# 2Leonardo_PCB.net
KiCad netlist of a schematic drawn in Altium Designer
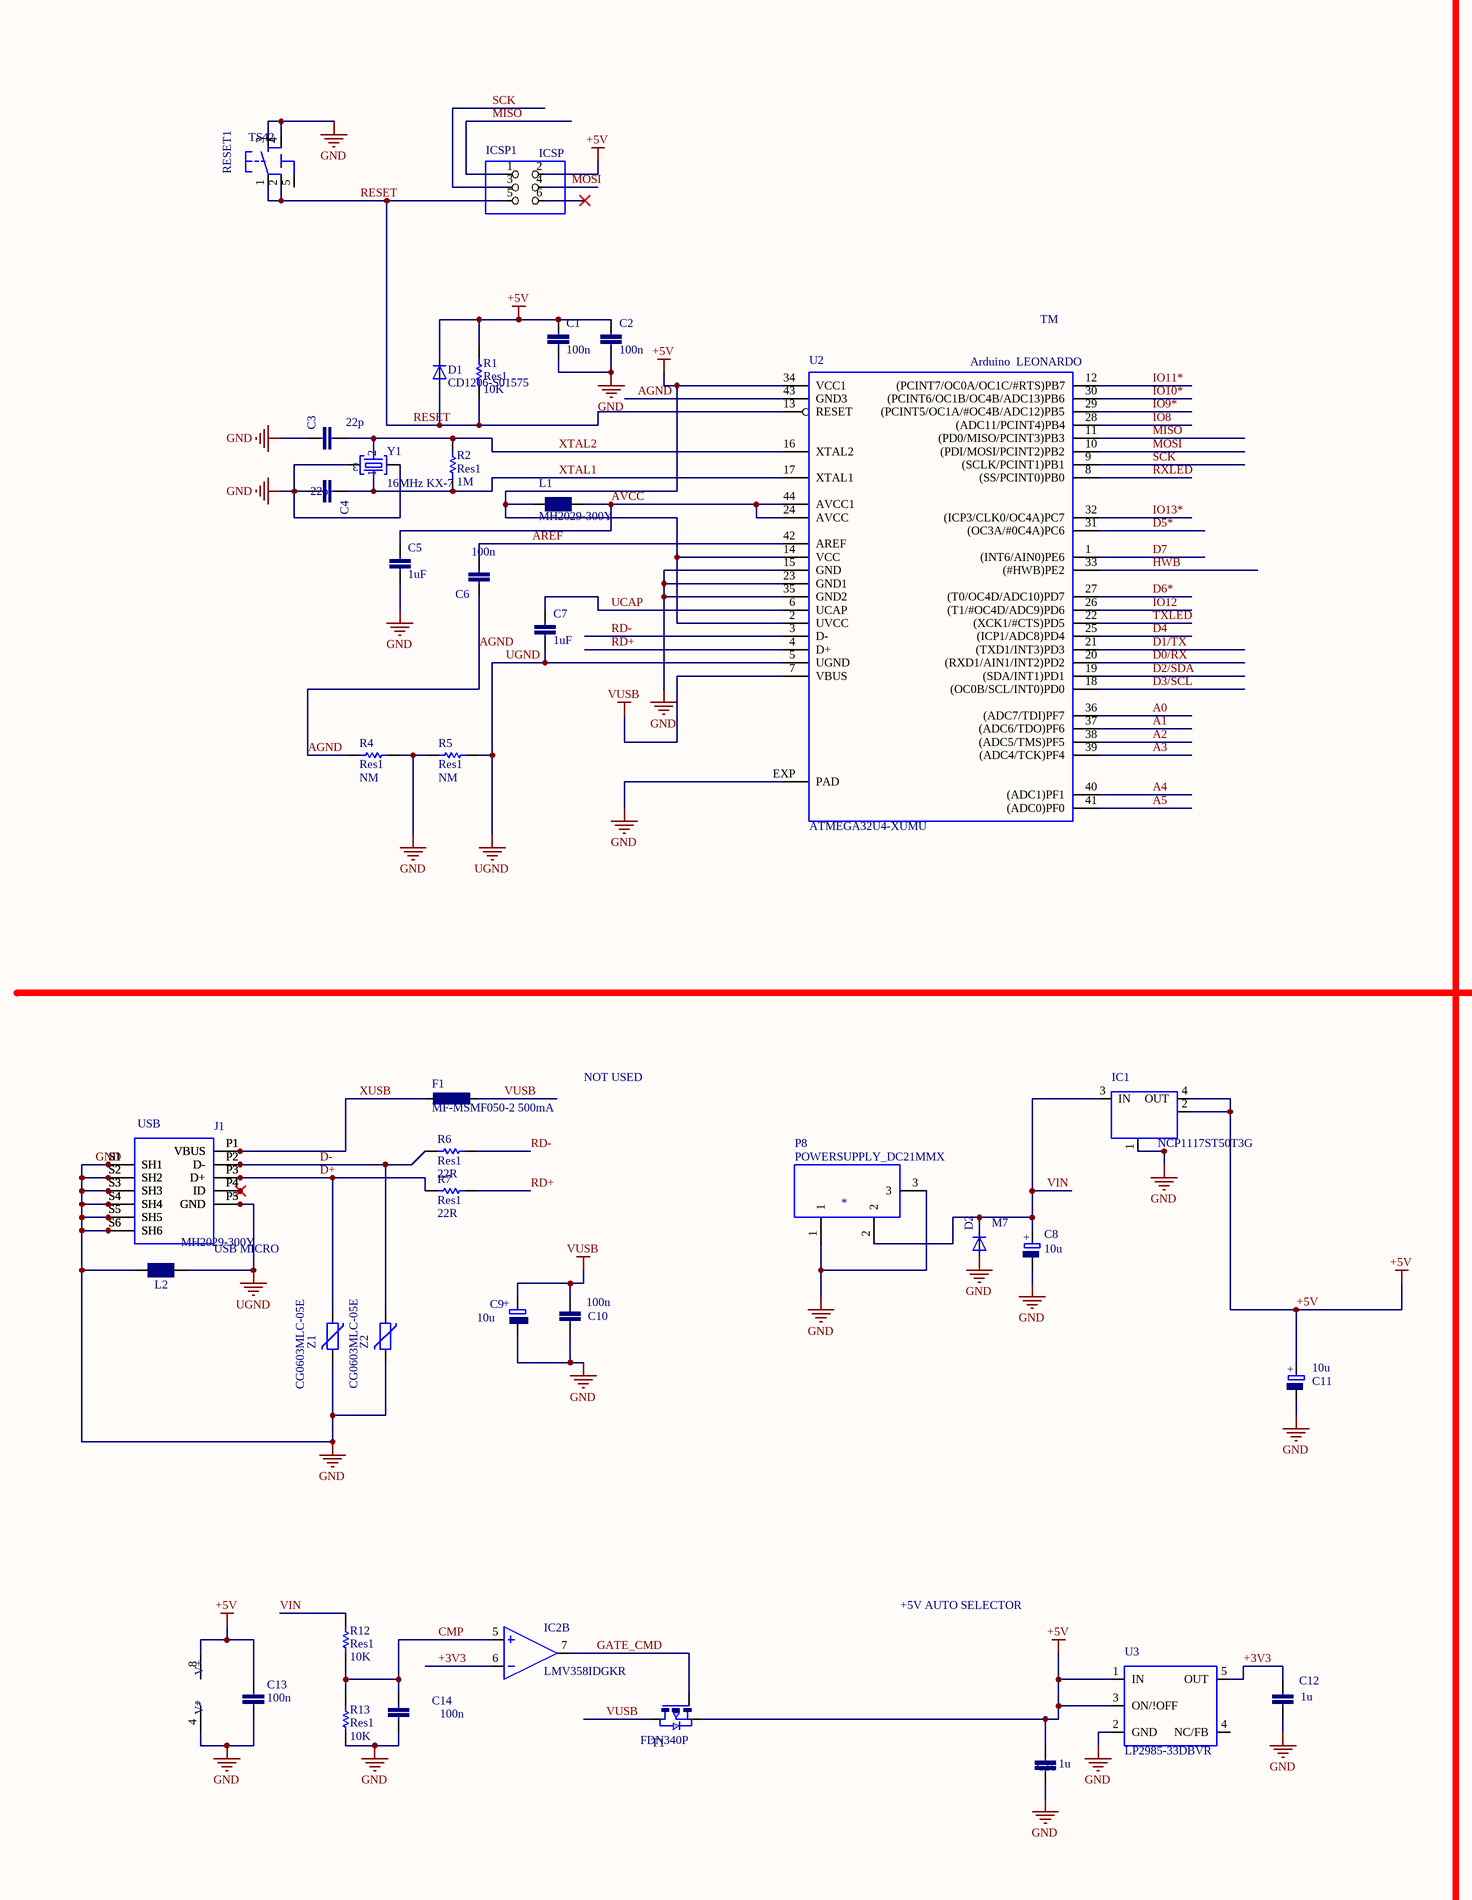
[diagram p0: 2Leonardo_PCB.SchDoc, left]
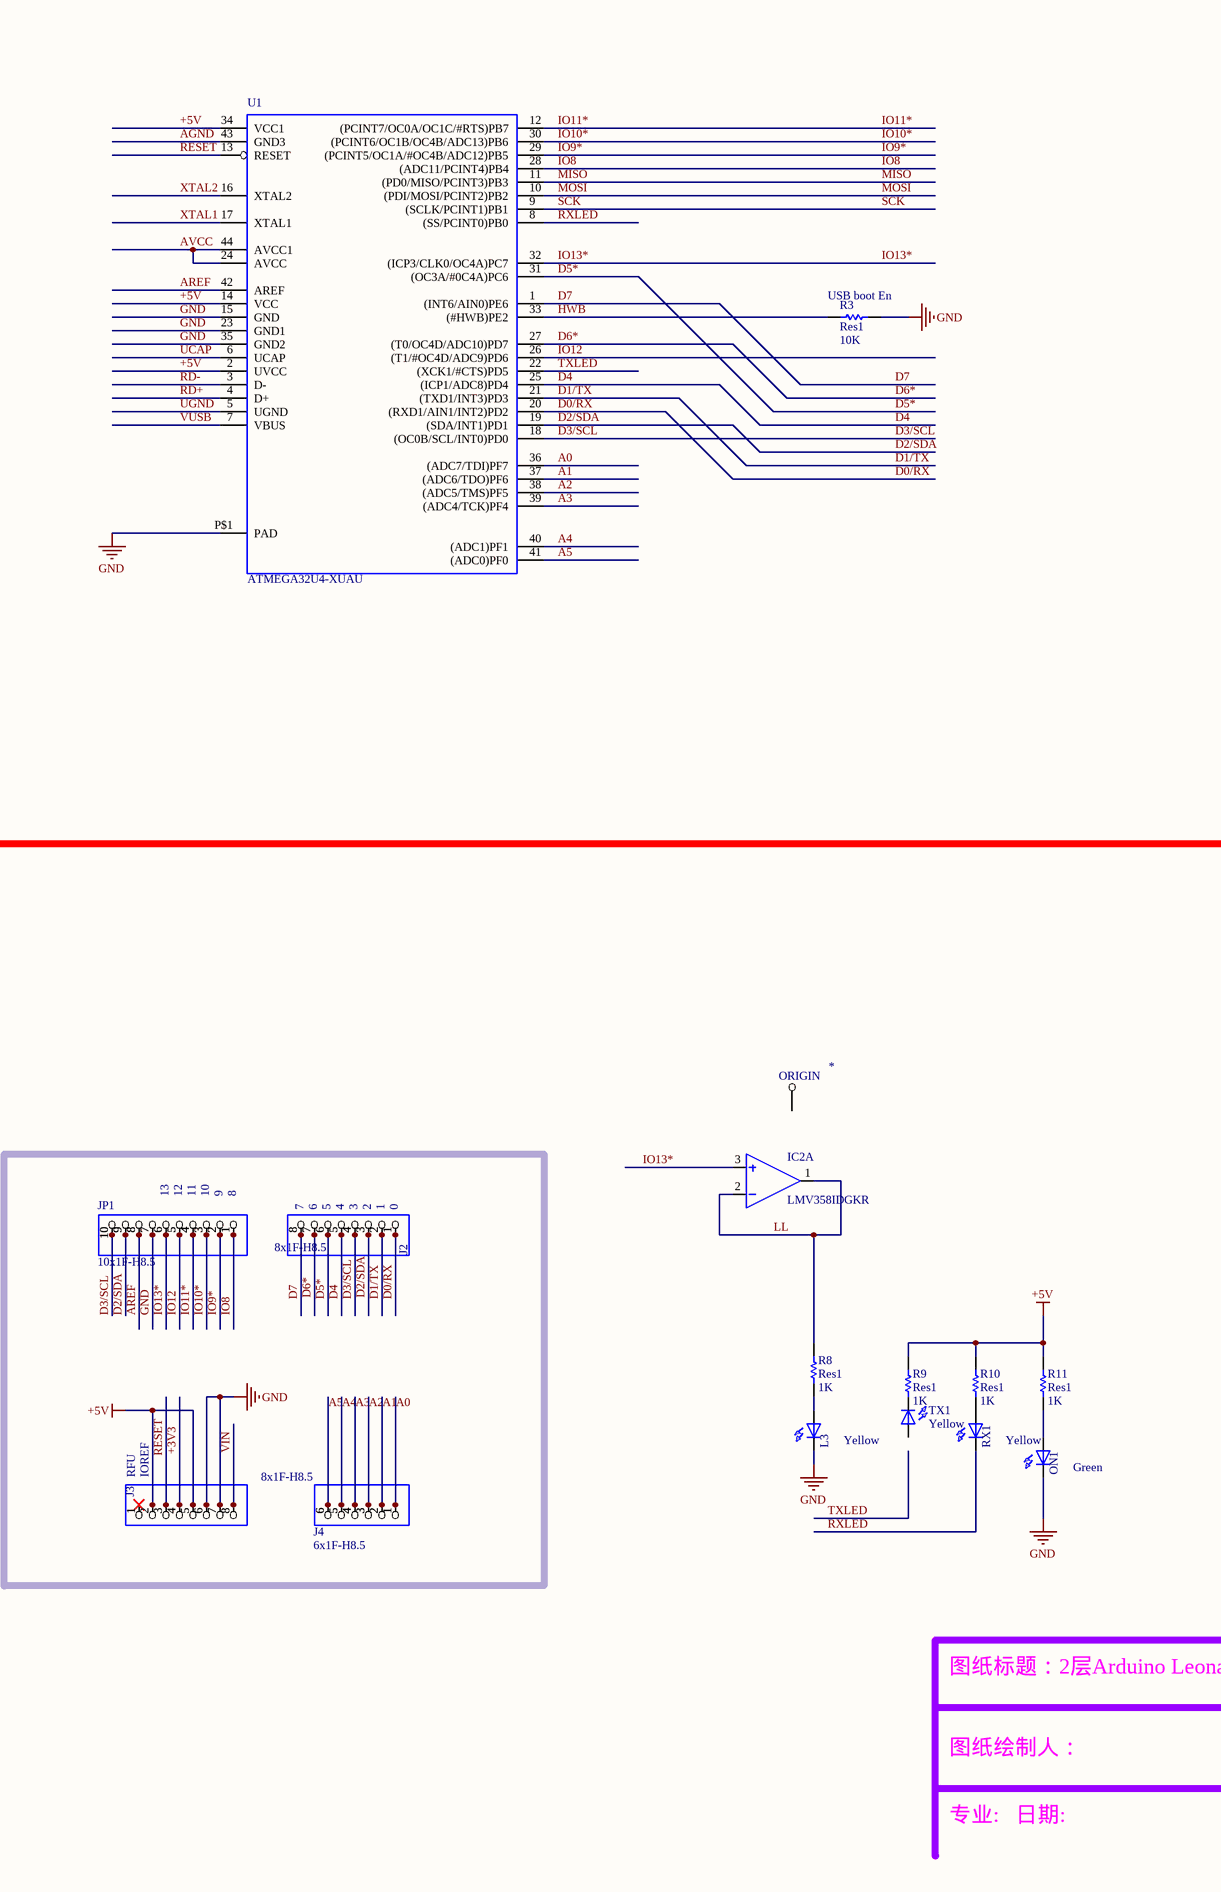
[diagram p1: 2Leonardo_PCB.SchDoc, right]

(export (version "E")
  (design (tool "Eeschema 10.0.6"))
  (components
    (comp (ref "C1") (value "100n") (footprint "C0603-ROUND") (libsource (lib "SmartPrj") (part "C-EUC0603")))
    (comp (ref "C2") (value "100n") (footprint "C0603-ROUND") (libsource (lib "SmartPrj") (part "C-EUC0603")))
    (comp (ref "C3") (value "22p") (footprint "C0603-ROUND") (libsource (lib "") (part "C-EUC0603_1")))
    (comp (ref "C4") (value "22p") (footprint "C0603-ROUND") (libsource (lib "") (part "C-EUC0603_3")))
    (comp (ref "C5") (value "1uF") (footprint "C0603-ROUND") (libsource (lib "SmartPrj") (part "C-EUC0603")))
    (comp (ref "C6") (value "100n") (footprint "C0603-ROUND") (libsource (lib "") (part "C-EUC0603_2")))
    (comp (ref "C7") (value "1uF") (footprint "C0603-ROUND") (libsource (lib "SmartPrj") (part "C-EUC0603")))
    (comp (ref "C8") (value "10u") (footprint "SMC_B") (libsource (lib "") (part "CPOL-EUSMCB_1")))
    (comp (ref "C9") (value "10u") (footprint "SMC_B") (libsource (lib "rcl") (part "CPOL-EUSMCB")))
    (comp (ref "C10") (value "100n") (footprint "C0603-ROUND") (libsource (lib "") (part "C-EUC0603_1")))
    (comp (ref "C11") (value "10u") (footprint "SMC_B") (libsource (lib "") (part "CPOL-EUSMCB_1")))
    (comp (ref "C12") (value "1u") (footprint "C0603-ROUND") (libsource (lib "") (part "C-EUC0603_2")))
    (comp (ref "C13")
      (value "100n")
      (footprint "C0603-ROUND")
      (libsource (lib "SmartPrj") (part "C-EUC0603"))
    )
    (comp (ref "C14") (value "100n") (footprint "C0603-ROUND") (libsource (lib "") (part "C-EUC0603_1")))
    (comp (ref "C15") (value "1u") (footprint "C0603-ROUND") (libsource (lib "") (part "C-EUC0603_1")))
    (comp (ref "D1")
      (value "CD1206-S01575")
      (footprint "MINIMELF")
      (libsource (lib "Leonardo") (part "DIODE-MINIMELF"))
    )
    (comp (ref "D2") (value "M7") (footprint "SMB") (libsource (lib "diode") (part "DIODE-SMB")))
    (comp (ref "F1")
      (value "MF-MSMF050-2 500mA")
      (footprint "L1812")
      (libsource (lib "rcl") (part "L-EUL1812"))
    )
    (comp (ref "IC1")
      (value "NCP1117ST50T3G")
      (footprint "SOT223")
      (libsource (lib "linear") (part "MC33269ST-3.3T3"))
    )
    (comp (ref "IC2")
      (value "LMV358IDGKR")
      (footprint "MSOP08")
      (libsource (lib "linear") (part "LMV358MMX"))
    )
    (comp (ref "ICSP1") (value "ICSP") (footprint "2X03") (libsource (lib "SmartPrj") (part "PINHD-2X3")))
    (comp (ref "J1")
      (value "USB MICRO")
      (footprint "CON2_USB_MICRO_B_AT")
      (libsource (lib "SmartPrj") (part "MYCON2_USB-MINI-B"))
    )
    (comp (ref "J2") (value "8x1F-H8.5") (footprint "1X08") (libsource (lib "SmartPrj") (part "PINHD-1X8")))
    (comp (ref "J3") (value "8x1F-H8.5") (footprint "1X08") (libsource (lib "SmartPrj") (part "PINHD-1X8")))
    (comp (ref "J4") (value "6x1F-H8.5") (footprint "1X06") (libsource (lib "Leonardo") (part "PINHD-1X6")))
    (comp (ref "JP1")
      (value "10x1F-H8.5")
      (footprint "1X10")
      (libsource (lib "Leonardo") (part "PINHD-1X10"))
    )
    (comp (ref "L1") (value "MH2029-300Y") (footprint "0805") (libsource (lib "") (part "WE-CBF_0805_1")))
    (comp (ref "L2")
      (value "MH2029-300Y")
      (footprint "0805")
      (libsource (lib "wuerth-elektronik") (part "WE-CBF_0805"))
    )
    (comp (ref "L3")
      (value "Yellow")
      (footprint "CHIPLED_0805")
      (libsource (lib "led") (part "LEDCHIPLED_0805"))
    )
    (comp (ref "ON1")
      (value "Green")
      (footprint "CHIPLED_0805")
      (libsource (lib "led") (part "LEDCHIPLED_0805"))
    )
    (comp (ref "ORIGIN1") (value "*") (footprint "FIDUCIA-MOUNT") (libsource (lib "SmartPrj") (part "TP_SP")))
    (comp (ref "P1")
      (value "*")
      (footprint "POWERSUPPLY_DC-21MM")
      (libsource (lib "SmartPrj") (part "POWERSUPPLY_DC21MMX"))
    )
    (comp (ref "R1")
      (value "Res1")
      (footprint "R0603-ROUND")
      (description "Resistor")
      (fields (field (name "ALTIUM_VALUE") "10K") (field (name "PUBLISHER") "Altium Limited"))
      (libsource (lib "Miscellaneous Devices") (part "Res1"))
    )
    (comp (ref "R2")
      (value "Res1")
      (footprint "R0603-ROUND")
      (description "Resistor")
      (fields (field (name "ALTIUM_VALUE") "1M") (field (name "PUBLISHER") "Altium Limited"))
      (libsource (lib "Miscellaneous Devices") (part "Res1"))
    )
    (comp (ref "R3")
      (value "Res1")
      (footprint "R0603-ROUND")
      (description "Resistor")
      (fields (field (name "ALTIUM_VALUE") "10K") (field (name "PUBLISHER") "Altium Limited"))
      (libsource (lib "Miscellaneous Devices") (part "Res1"))
    )
    (comp (ref "R4")
      (value "Res1")
      (footprint "R0603-ROUND")
      (description "Resistor")
      (fields (field (name "ALTIUM_VALUE") "NM") (field (name "PUBLISHER") "Altium Limited"))
      (libsource (lib "Miscellaneous Devices") (part "Res1"))
    )
    (comp (ref "R5")
      (value "Res1")
      (footprint "R0603-ROUND")
      (description "Resistor")
      (fields (field (name "ALTIUM_VALUE") "NM") (field (name "PUBLISHER") "Altium Limited"))
      (libsource (lib "Miscellaneous Devices") (part "Res1"))
    )
    (comp (ref "R6")
      (value "Res1")
      (footprint "R0603-ROUND")
      (description "Resistor")
      (fields (field (name "ALTIUM_VALUE") "22R") (field (name "PUBLISHER") "Altium Limited"))
      (libsource (lib "Miscellaneous Devices") (part "Res1"))
    )
    (comp (ref "R7")
      (value "Res1")
      (footprint "R0603-ROUND")
      (description "Resistor")
      (fields (field (name "ALTIUM_VALUE") "22R") (field (name "PUBLISHER") "Altium Limited"))
      (libsource (lib "Miscellaneous Devices") (part "Res1"))
    )
    (comp (ref "R8")
      (value "Res1")
      (footprint "R0603-ROUND")
      (description "Resistor")
      (fields (field (name "ALTIUM_VALUE") "1K") (field (name "PUBLISHER") "Altium Limited"))
      (libsource (lib "Miscellaneous Devices") (part "Res1"))
    )
    (comp (ref "R9")
      (value "Res1")
      (footprint "R0603-ROUND")
      (description "Resistor")
      (fields (field (name "ALTIUM_VALUE") "1K") (field (name "PUBLISHER") "Altium Limited"))
      (libsource (lib "Miscellaneous Devices") (part "Res1"))
    )
    (comp (ref "R10")
      (value "Res1")
      (footprint "R0603-ROUND")
      (description "Resistor")
      (fields (field (name "ALTIUM_VALUE") "1K") (field (name "PUBLISHER") "Altium Limited"))
      (libsource (lib "Miscellaneous Devices") (part "Res1"))
    )
    (comp (ref "R11")
      (value "Res1")
      (footprint "R0603-ROUND")
      (description "Resistor")
      (fields (field (name "ALTIUM_VALUE") "1K") (field (name "PUBLISHER") "Altium Limited"))
      (libsource (lib "Miscellaneous Devices") (part "Res1"))
    )
    (comp (ref "R12")
      (value "Res1")
      (footprint "R0603-ROUND")
      (description "Resistor")
      (fields (field (name "ALTIUM_VALUE") "10K") (field (name "PUBLISHER") "Altium Limited"))
      (libsource (lib "Miscellaneous Devices") (part "Res1"))
    )
    (comp (ref "R13")
      (value "Res1")
      (footprint "R0603-ROUND")
      (description "Resistor")
      (fields (field (name "ALTIUM_VALUE") "10K") (field (name "PUBLISHER") "Altium Limited"))
      (libsource (lib "Miscellaneous Devices") (part "Res1"))
    )
    (comp (ref "RESET1") (value "TS42") (footprint "TS42") (libsource (lib "SmartPrj") (part "TS42")))
    (comp (ref "RX1")
      (value "Yellow")
      (footprint "CHIPLED_0805")
      (libsource (lib "led") (part "LEDCHIPLED_0805"))
    )
    (comp (ref "T1") (value "FDN340P") (footprint "SOT-23") (libsource (lib "zetex") (part "PMOSSOT23")))
    (comp (ref "TX1")
      (value "Yellow")
      (footprint "CHIPLED_0805")
      (libsource (lib "led") (part "LEDCHIPLED_0805"))
    )
    (comp (ref "U1")
      (value "ATMEGA32U4-XUAU")
      (footprint "TQFP44-PAD")
      (libsource (lib "SmartPrj") (part "ATMEGA32U4-XUAU"))
    )
    (comp (ref "U2")
      (value "ATMEGA32U4-XUMU")
      (footprint "QFN44ML7X7")
      (libsource (lib "SmartPrj") (part "ATMEGA32U4-XUMU"))
    )
    (comp (ref "U3")
      (value "LP2985-33DBVR")
      (footprint "SOT23-DBV")
      (libsource (lib "SmartPrj") (part "LP2985-XXDBVR33"))
    )
    (comp (ref "Y1")
      (value "16MHz KX-7")
      (footprint "CRYSTAL-3.2-2.5")
      (libsource (lib "SmartPrj") (part "CRYSTAL-3.2-2.5"))
    )
    (comp (ref "Z1")
      (value "CG0603MLC-05E")
      (footprint "CT/CN0603")
      (libsource (lib "varistor") (part "VARISTORCN0603"))
    )
    (comp (ref "Z2")
      (value "CG0603MLC-05E")
      (footprint "CT/CN0603")
      (libsource (lib "varistor") (part "VARISTORCN0603"))
    )
  )
  (nets
    (net (code "1") (name "+5V") (class "Default")
      (node (ref "C1") (pin "1") (pinfunction "1_1") (pintype "passive"))
      (node (ref "C11") (pin "+") (pinfunction "+_+") (pintype "passive"))
      (node (ref "C13") (pin "1") (pinfunction "1_1") (pintype "passive"))
      (node (ref "C15") (pin "2") (pinfunction "2_2") (pintype "passive"))
      (node (ref "C2") (pin "1") (pinfunction "1_1") (pintype "passive"))
      (node (ref "D1") (pin "C") (pinfunction "C_C") (pintype "passive"))
      (node (ref "IC1") (pin "2") (pinfunction "OUT@1_2") (pintype "passive"))
      (node (ref "IC1") (pin "4") (pinfunction "OUT_4") (pintype "passive"))
      (node (ref "IC2") (pin "8") (pinfunction "V+_8") (pintype "passive"))
      (node (ref "ICSP1") (pin "2") (pinfunction "2_2") (pintype "passive"))
      (node (ref "J3") (pin "2") (pinfunction "2_2") (pintype "passive"))
      (node (ref "J3") (pin "5") (pinfunction "5_5") (pintype "passive"))
      (node (ref "L1") (pin "1") (pinfunction "1_1") (pintype "passive"))
      (node (ref "R1") (pin "2") (pinfunction "2_2") (pintype "passive"))
      (node (ref "R10") (pin "2") (pinfunction "2_2") (pintype "passive"))
      (node (ref "R11") (pin "2") (pinfunction "2_2") (pintype "passive"))
      (node (ref "R9") (pin "2") (pinfunction "2_2") (pintype "passive"))
      (node (ref "T1") (pin "2") (pinfunction "S_2") (pintype "passive"))
      (node (ref "U1") (pin "14") (pinfunction "VCC_14") (pintype "passive"))
      (node (ref "U1") (pin "2") (pinfunction "UVCC_2") (pintype "passive"))
      (node (ref "U1") (pin "34") (pinfunction "VCC1_34") (pintype "passive"))
      (node (ref "U2") (pin "14") (pinfunction "VCC_14") (pintype "passive"))
      (node (ref "U2") (pin "2") (pinfunction "UVCC_2") (pintype "passive"))
      (node (ref "U2") (pin "34") (pinfunction "VCC1_34") (pintype "passive"))
      (node (ref "U3") (pin "1") (pinfunction "IN_1") (pintype "passive"))
      (node (ref "U3") (pin "3") (pinfunction "ON/!OFF_3") (pintype "passive"))
    )
    (net (code "2") (name "/+3V3") (class "Default")
      (node (ref "C12") (pin "2") (pinfunction "2_2") (pintype "passive"))
      (node (ref "IC2") (pin "6") (pinfunction "-IN_6") (pintype "passive"))
      (node (ref "J3") (pin "4") (pinfunction "4_4") (pintype "passive"))
      (node (ref "U3") (pin "5") (pinfunction "OUT_5") (pintype "passive"))
    )
    (net (code "3") (name "/A0") (class "Default")
      (node (ref "J4") (pin "1") (pinfunction "1_1") (pintype "passive"))
      (node (ref "U1") (pin "36") (pinfunction "(ADC7/TDI)PF7_36") (pintype "passive"))
      (node (ref "U2") (pin "36") (pinfunction "(ADC7/TDI)PF7_36") (pintype "passive"))
    )
    (net (code "4") (name "/A1") (class "Default")
      (node (ref "J4") (pin "2") (pinfunction "2_2") (pintype "passive"))
      (node (ref "U1") (pin "37") (pinfunction "(ADC6/TDO)PF6_37") (pintype "passive"))
      (node (ref "U2") (pin "37") (pinfunction "(ADC6/TDO)PF6_37") (pintype "passive"))
    )
    (net (code "5") (name "/A2") (class "Default")
      (node (ref "J4") (pin "3") (pinfunction "3_3") (pintype "passive"))
      (node (ref "U1") (pin "38") (pinfunction "(ADC5/TMS)PF5_38") (pintype "passive"))
      (node (ref "U2") (pin "38") (pinfunction "(ADC5/TMS)PF5_38") (pintype "passive"))
    )
    (net (code "6") (name "/A3") (class "Default")
      (node (ref "J4") (pin "4") (pinfunction "4_4") (pintype "passive"))
      (node (ref "U1") (pin "39") (pinfunction "(ADC4/TCK)PF4_39") (pintype "passive"))
      (node (ref "U2") (pin "39") (pinfunction "(ADC4/TCK)PF4_39") (pintype "passive"))
    )
    (net (code "7") (name "/A4") (class "Default")
      (node (ref "J4") (pin "5") (pinfunction "5_5") (pintype "passive"))
      (node (ref "U1") (pin "40") (pinfunction "(ADC1)PF1_40") (pintype "passive"))
      (node (ref "U2") (pin "40") (pinfunction "(ADC1)PF1_40") (pintype "passive"))
    )
    (net (code "8") (name "/A5") (class "Default")
      (node (ref "J4") (pin "6") (pinfunction "6_6") (pintype "passive"))
      (node (ref "U1") (pin "41") (pinfunction "(ADC0)PF0_41") (pintype "passive"))
      (node (ref "U2") (pin "41") (pinfunction "(ADC0)PF0_41") (pintype "passive"))
    )
    (net (code "9") (name "/AGND") (class "Default")
      (node (ref "C6") (pin "1") (pinfunction "1_1") (pintype "passive"))
      (node (ref "R4") (pin "1") (pinfunction "1_1") (pintype "passive"))
      (node (ref "U1") (pin "43") (pinfunction "GND3_43") (pintype "passive"))
      (node (ref "U2") (pin "43") (pinfunction "GND3_43") (pintype "passive"))
    )
    (net (code "10") (name "/AREF") (class "Default")
      (node (ref "C6") (pin "2") (pinfunction "2_2") (pintype "passive"))
      (node (ref "JP1") (pin "8") (pinfunction "8_8") (pintype "passive"))
      (node (ref "U1") (pin "42") (pinfunction "AREF_42") (pintype "passive"))
      (node (ref "U2") (pin "42") (pinfunction "AREF_42") (pintype "passive"))
    )
    (net (code "11") (name "/AVCC") (class "Default")
      (node (ref "C5") (pin "1") (pinfunction "1_1") (pintype "passive"))
      (node (ref "L1") (pin "2") (pinfunction "2_2") (pintype "passive"))
      (node (ref "U1") (pin "24") (pinfunction "AVCC_24") (pintype "passive"))
      (node (ref "U1") (pin "44") (pinfunction "AVCC1_44") (pintype "passive"))
      (node (ref "U2") (pin "24") (pinfunction "AVCC_24") (pintype "passive"))
      (node (ref "U2") (pin "44") (pinfunction "AVCC1_44") (pintype "passive"))
    )
    (net (code "12") (name "/CMP") (class "Default")
      (node (ref "C14") (pin "2") (pinfunction "2_2") (pintype "passive"))
      (node (ref "IC2") (pin "5") (pinfunction "+IN_5") (pintype "passive"))
      (node (ref "R12") (pin "1") (pinfunction "1_1") (pintype "passive"))
      (node (ref "R13") (pin "2") (pinfunction "2_2") (pintype "passive"))
    )
    (net (code "13") (name "/D+") (class "Default")
      (node (ref "J1") (pin "P3") (pinfunction "D+_P3") (pintype "passive"))
      (node (ref "R7") (pin "1") (pinfunction "1_1") (pintype "passive"))
      (node (ref "Z1") (pin "1") (pinfunction "1_1") (pintype "passive"))
    )
    (net (code "14") (name "/D-") (class "Default")
      (node (ref "J1") (pin "P2") (pinfunction "D-_P2") (pintype "passive"))
      (node (ref "R6") (pin "1") (pinfunction "1_1") (pintype "passive"))
      (node (ref "Z2") (pin "1") (pinfunction "1_1") (pintype "passive"))
    )
    (net (code "15") (name "/D0{slash}RX") (class "Default")
      (node (ref "J2") (pin "1") (pinfunction "1_1") (pintype "passive"))
      (node (ref "U1") (pin "20") (pinfunction "(RXD1/AIN1/INT2)PD2_20") (pintype "passive"))
      (node (ref "U2") (pin "20") (pinfunction "(RXD1/AIN1/INT2)PD2_20") (pintype "passive"))
    )
    (net (code "16") (name "/D1{slash}TX") (class "Default")
      (node (ref "J2") (pin "2") (pinfunction "2_2") (pintype "passive"))
      (node (ref "U1") (pin "21") (pinfunction "(TXD1/INT3)PD3_21") (pintype "passive"))
      (node (ref "U2") (pin "21") (pinfunction "(TXD1/INT3)PD3_21") (pintype "passive"))
    )
    (net (code "17") (name "/D2{slash}SDA") (class "Default")
      (node (ref "J2") (pin "3") (pinfunction "3_3") (pintype "passive"))
      (node (ref "JP1") (pin "9") (pinfunction "9_9") (pintype "passive"))
      (node (ref "U1") (pin "19") (pinfunction "(SDA/INT1)PD1_19") (pintype "passive"))
      (node (ref "U2") (pin "19") (pinfunction "(SDA/INT1)PD1_19") (pintype "passive"))
    )
    (net (code "18") (name "/D3{slash}SCL") (class "Default")
      (node (ref "J2") (pin "4") (pinfunction "4_4") (pintype "passive"))
      (node (ref "JP1") (pin "10") (pinfunction "10_10") (pintype "passive"))
      (node (ref "U1") (pin "18") (pinfunction "(OC0B/SCL/INT0)PD0_18") (pintype "passive"))
      (node (ref "U2") (pin "18") (pinfunction "(OC0B/SCL/INT0)PD0_18") (pintype "passive"))
    )
    (net (code "19") (name "/D4") (class "Default")
      (node (ref "J2") (pin "5") (pinfunction "5_5") (pintype "passive"))
      (node (ref "U1") (pin "25") (pinfunction "(ICP1/ADC8)PD4_25") (pintype "passive"))
      (node (ref "U2") (pin "25") (pinfunction "(ICP1/ADC8)PD4_25") (pintype "passive"))
    )
    (net (code "20") (name "/D5*") (class "Default")
      (node (ref "J2") (pin "6") (pinfunction "6_6") (pintype "passive"))
      (node (ref "U1") (pin "31") (pinfunction "(OC3A/#0C4A)PC6_31") (pintype "passive"))
      (node (ref "U2") (pin "31") (pinfunction "(OC3A/#0C4A)PC6_31") (pintype "passive"))
    )
    (net (code "21") (name "/D6*") (class "Default")
      (node (ref "J2") (pin "7") (pinfunction "7_7") (pintype "passive"))
      (node (ref "U1") (pin "27") (pinfunction "(T0/OC4D/ADC10)PD7_27") (pintype "passive"))
      (node (ref "U2") (pin "27") (pinfunction "(T0/OC4D/ADC10)PD7_27") (pintype "passive"))
    )
    (net (code "22") (name "/D7") (class "Default")
      (node (ref "J2") (pin "8") (pinfunction "8_8") (pintype "passive"))
      (node (ref "U1") (pin "1") (pinfunction "(INT6/AIN0)PE6_1") (pintype "passive"))
      (node (ref "U2") (pin "1") (pinfunction "(INT6/AIN0)PE6_1") (pintype "passive"))
    )
    (net (code "23") (name "/GATE_CMD") (class "Default")
      (node (ref "IC2") (pin "7") (pinfunction "OUT_7") (pintype "passive"))
      (node (ref "T1") (pin "3") (pinfunction "G_3") (pintype "passive"))
    )
    (net (code "24") (name "/HWB") (class "Default")
      (node (ref "R3") (pin "2") (pinfunction "2_2") (pintype "passive"))
      (node (ref "U1") (pin "33") (pinfunction "(#HWB)PE2_33") (pintype "passive"))
      (node (ref "U2") (pin "33") (pinfunction "(#HWB)PE2_33") (pintype "passive"))
    )
    (net (code "25") (name "/IO8") (class "Default")
      (node (ref "JP1") (pin "1") (pinfunction "1_1") (pintype "passive"))
      (node (ref "U1") (pin "28") (pinfunction "(ADC11/PCINT4)PB4_28") (pintype "passive"))
      (node (ref "U2") (pin "28") (pinfunction "(ADC11/PCINT4)PB4_28") (pintype "passive"))
    )
    (net (code "26") (name "/IO9*") (class "Default")
      (node (ref "JP1") (pin "2") (pinfunction "2_2") (pintype "passive"))
      (node (ref "U1") (pin "29") (pinfunction "(PCINT5/OC1A/#OC4B/ADC12)PB5_29") (pintype "passive"))
      (node (ref "U2") (pin "29") (pinfunction "(PCINT5/OC1A/#OC4B/ADC12)PB5_29") (pintype "passive"))
    )
    (net (code "27") (name "/IO10*") (class "Default")
      (node (ref "JP1") (pin "3") (pinfunction "3_3") (pintype "passive"))
      (node (ref "U1") (pin "30") (pinfunction "(PCINT6/OC1B/OC4B/ADC13)PB6_30") (pintype "passive"))
      (node (ref "U2") (pin "30") (pinfunction "(PCINT6/OC1B/OC4B/ADC13)PB6_30") (pintype "passive"))
    )
    (net (code "28") (name "/IO11*") (class "Default")
      (node (ref "JP1") (pin "4") (pinfunction "4_4") (pintype "passive"))
      (node (ref "U1") (pin "12") (pinfunction "(PCINT7/OC0A/OC1C/#RTS)PB7_12") (pintype "passive"))
      (node (ref "U2") (pin "12") (pinfunction "(PCINT7/OC0A/OC1C/#RTS)PB7_12") (pintype "passive"))
    )
    (net (code "29") (name "/IO12") (class "Default")
      (node (ref "JP1") (pin "5") (pinfunction "5_5") (pintype "passive"))
      (node (ref "U1") (pin "26") (pinfunction "(T1/#OC4D/ADC9)PD6_26") (pintype "passive"))
      (node (ref "U2") (pin "26") (pinfunction "(T1/#OC4D/ADC9)PD6_26") (pintype "passive"))
    )
    (net (code "30") (name "/IO13*") (class "Default")
      (node (ref "IC2") (pin "3") (pinfunction "+IN_3") (pintype "passive"))
      (node (ref "JP1") (pin "6") (pinfunction "6_6") (pintype "passive"))
      (node (ref "U1") (pin "32") (pinfunction "(ICP3/CLK0/OC4A)PC7_32") (pintype "passive"))
      (node (ref "U2") (pin "32") (pinfunction "(ICP3/CLK0/OC4A)PC7_32") (pintype "passive"))
    )
    (net (code "31") (name "/LL") (class "Default")
      (node (ref "IC2") (pin "1") (pinfunction "OUT_1") (pintype "passive"))
      (node (ref "IC2") (pin "2") (pinfunction "-IN_2") (pintype "passive"))
      (node (ref "R8") (pin "2") (pinfunction "2_2") (pintype "passive"))
    )
    (net (code "32") (name "/MISO") (class "Default")
      (node (ref "ICSP1") (pin "1") (pinfunction "1_1") (pintype "passive"))
      (node (ref "U1") (pin "11") (pinfunction "(PD0/MISO/PCINT3)PB3_11") (pintype "passive"))
      (node (ref "U2") (pin "11") (pinfunction "(PD0/MISO/PCINT3)PB3_11") (pintype "passive"))
    )
    (net (code "33") (name "/MOSI") (class "Default")
      (node (ref "ICSP1") (pin "4") (pinfunction "4_4") (pintype "passive"))
      (node (ref "U1") (pin "10") (pinfunction "(PDI/MOSI/PCINT2)PB2_10") (pintype "passive"))
      (node (ref "U2") (pin "10") (pinfunction "(PDI/MOSI/PCINT2)PB2_10") (pintype "passive"))
    )
    (net (code "34") (name "/RD+") (class "Default")
      (node (ref "R7") (pin "2") (pinfunction "2_2") (pintype "passive"))
      (node (ref "U1") (pin "4") (pinfunction "D+_4") (pintype "passive"))
      (node (ref "U2") (pin "4") (pinfunction "D+_4") (pintype "passive"))
    )
    (net (code "35") (name "/RD-") (class "Default")
      (node (ref "R6") (pin "2") (pinfunction "2_2") (pintype "passive"))
      (node (ref "U1") (pin "3") (pinfunction "D-_3") (pintype "passive"))
      (node (ref "U2") (pin "3") (pinfunction "D-_3") (pintype "passive"))
    )
    (net (code "36") (name "/RESET") (class "Default")
      (node (ref "D1") (pin "A") (pinfunction "A_A") (pintype "passive"))
      (node (ref "ICSP1") (pin "5") (pinfunction "5_5") (pintype "passive"))
      (node (ref "J3") (pin "3") (pinfunction "3_3") (pintype "passive"))
      (node (ref "R1") (pin "1") (pinfunction "1_1") (pintype "passive"))
      (node (ref "RESET1") (pin "1") (pinfunction "1_1") (pintype "passive"))
      (node (ref "RESET1") (pin "2") (pinfunction "2_2") (pintype "passive"))
      (node (ref "U1") (pin "13") (pinfunction "RESET_13") (pintype "passive"))
      (node (ref "U2") (pin "13") (pinfunction "RESET_13") (pintype "passive"))
    )
    (net (code "37") (name "/RXLED") (class "Default")
      (node (ref "RX1") (pin "C") (pinfunction "C_C") (pintype "passive"))
      (node (ref "U1") (pin "8") (pinfunction "(SS/PCINT0)PB0_8") (pintype "passive"))
      (node (ref "U2") (pin "8") (pinfunction "(SS/PCINT0)PB0_8") (pintype "passive"))
    )
    (net (code "38") (name "/SCK") (class "Default")
      (node (ref "ICSP1") (pin "3") (pinfunction "3_3") (pintype "passive"))
      (node (ref "U1") (pin "9") (pinfunction "(SCLK/PCINT1)PB1_9") (pintype "passive"))
      (node (ref "U2") (pin "9") (pinfunction "(SCLK/PCINT1)PB1_9") (pintype "passive"))
    )
    (net (code "39") (name "/TXLED") (class "Default")
      (node (ref "U1") (pin "22") (pinfunction "(XCK1/#CTS)PD5_22") (pintype "passive"))
      (node (ref "U2") (pin "22") (pinfunction "(XCK1/#CTS)PD5_22") (pintype "passive"))
    )
    (net (code "40") (name "/UCAP") (class "Default")
      (node (ref "C7") (pin "1") (pinfunction "1_1") (pintype "passive"))
      (node (ref "U1") (pin "6") (pinfunction "UCAP_6") (pintype "passive"))
      (node (ref "U2") (pin "6") (pinfunction "UCAP_6") (pintype "passive"))
    )
    (net (code "41") (name "/VIN") (class "Default")
      (node (ref "C8") (pin "+") (pinfunction "+_+") (pintype "passive"))
      (node (ref "D2") (pin "C") (pinfunction "C_C") (pintype "passive"))
      (node (ref "IC1") (pin "3") (pinfunction "IN_3") (pintype "passive"))
      (node (ref "J3") (pin "8") (pinfunction "8_8") (pintype "passive"))
      (node (ref "P1") (pin "2") (pinfunction "2_2") (pintype "passive"))
      (node (ref "R12") (pin "2") (pinfunction "2_2") (pintype "passive"))
    )
    (net (code "42") (name "/XTAL1") (class "Default")
      (node (ref "C4") (pin "1") (pinfunction "1_1") (pintype "passive"))
      (node (ref "R2") (pin "1") (pinfunction "1_1") (pintype "passive"))
      (node (ref "U1") (pin "17") (pinfunction "XTAL1_17") (pintype "passive"))
      (node (ref "U2") (pin "17") (pinfunction "XTAL1_17") (pintype "passive"))
      (node (ref "Y1") (pin "1") (pinfunction "C1_1") (pintype "passive"))
    )
    (net (code "43") (name "/XTAL2") (class "Default")
      (node (ref "C3") (pin "2") (pinfunction "2_2") (pintype "passive"))
      (node (ref "R2") (pin "2") (pinfunction "2_2") (pintype "passive"))
      (node (ref "U1") (pin "16") (pinfunction "XTAL2_16") (pintype "passive"))
      (node (ref "U2") (pin "16") (pinfunction "XTAL2_16") (pintype "passive"))
      (node (ref "Y1") (pin "3") (pinfunction "C2_3") (pintype "passive"))
    )
    (net (code "44") (name "/XUSB") (class "Default")
      (node (ref "F1") (pin "2") (pinfunction "2_2") (pintype "passive"))
      (node (ref "J1") (pin "P1") (pinfunction "VBUS_P1") (pintype "passive"))
    )
    (net (code "45") (name "GND") (class "Default")
      (node (ref "C1") (pin "2") (pinfunction "2_2") (pintype "passive"))
      (node (ref "C10") (pin "1") (pinfunction "1_1") (pintype "passive"))
      (node (ref "C11") (pin "-") (pinfunction "-_-") (pintype "passive"))
      (node (ref "C12") (pin "1") (pinfunction "1_1") (pintype "passive"))
      (node (ref "C13") (pin "2") (pinfunction "2_2") (pintype "passive"))
      (node (ref "C14") (pin "1") (pinfunction "1_1") (pintype "passive"))
      (node (ref "C15") (pin "1") (pinfunction "1_1") (pintype "passive"))
      (node (ref "C2") (pin "2") (pinfunction "2_2") (pintype "passive"))
      (node (ref "C3") (pin "1") (pinfunction "1_1") (pintype "passive"))
      (node (ref "C4") (pin "2") (pinfunction "2_2") (pintype "passive"))
      (node (ref "C5") (pin "2") (pinfunction "2_2") (pintype "passive"))
      (node (ref "C8") (pin "-") (pinfunction "-_-") (pintype "passive"))
      (node (ref "C9") (pin "-") (pinfunction "-_-") (pintype "passive"))
      (node (ref "D2") (pin "A") (pinfunction "A_A") (pintype "passive"))
      (node (ref "IC1") (pin "1") (pinfunction "GND/ADJ_1") (pintype "passive"))
      (node (ref "IC2") (pin "4") (pinfunction "V-_4") (pintype "passive"))
      (node (ref "J1") (pin "S1") (pinfunction "SH1_S1") (pintype "passive"))
      (node (ref "J1") (pin "S2") (pinfunction "SH2_S2") (pintype "passive"))
      (node (ref "J1") (pin "S3") (pinfunction "SH3_S3") (pintype "passive"))
      (node (ref "J1") (pin "S4") (pinfunction "SH4_S4") (pintype "passive"))
      (node (ref "J1") (pin "S5") (pinfunction "SH5_S5") (pintype "passive"))
      (node (ref "J1") (pin "S6") (pinfunction "SH6_S6") (pintype "passive"))
      (node (ref "J3") (pin "6") (pinfunction "6_6") (pintype "passive"))
      (node (ref "J3") (pin "7") (pinfunction "7_7") (pintype "passive"))
      (node (ref "JP1") (pin "7") (pinfunction "7_7") (pintype "passive"))
      (node (ref "L2") (pin "2") (pinfunction "2_2") (pintype "passive"))
      (node (ref "L3") (pin "C") (pinfunction "C_C") (pintype "passive"))
      (node (ref "ON1") (pin "C") (pinfunction "C_C") (pintype "passive"))
      (node (ref "P1") (pin "1") (pinfunction "1_1") (pintype "passive"))
      (node (ref "P1") (pin "3") (pinfunction "3_3") (pintype "passive"))
      (node (ref "R13") (pin "1") (pinfunction "1_1") (pintype "passive"))
      (node (ref "R3") (pin "1") (pinfunction "1_1") (pintype "passive"))
      (node (ref "R4") (pin "2") (pinfunction "2_2") (pintype "passive"))
      (node (ref "R5") (pin "1") (pinfunction "1_1") (pintype "passive"))
      (node (ref "RESET1") (pin "3") (pinfunction "3_3") (pintype "passive"))
      (node (ref "RESET1") (pin "4") (pinfunction "4_4") (pintype "passive"))
      (node (ref "U1") (pin "15") (pinfunction "GND_15") (pintype "passive"))
      (node (ref "U1") (pin "23") (pinfunction "GND1_23") (pintype "passive"))
      (node (ref "U1") (pin "35") (pinfunction "GND2_35") (pintype "passive"))
      (node (ref "U1") (pin "P$1") (pinfunction "PAD_P$1") (pintype "passive"))
      (node (ref "U2") (pin "15") (pinfunction "GND_15") (pintype "passive"))
      (node (ref "U2") (pin "23") (pinfunction "GND1_23") (pintype "passive"))
      (node (ref "U2") (pin "35") (pinfunction "GND2_35") (pintype "passive"))
      (node (ref "U2") (pin "EXP") (pinfunction "PAD_EXP") (pintype "passive"))
      (node (ref "U3") (pin "2") (pinfunction "GND_2") (pintype "passive"))
      (node (ref "Y1") (pin "2") (pinfunction "GND@1_2") (pintype "passive"))
      (node (ref "Y1") (pin "4") (pinfunction "GND@2_4") (pintype "passive"))
      (node (ref "Z1") (pin "2") (pinfunction "2_2") (pintype "passive"))
      (node (ref "Z2") (pin "2") (pinfunction "2_2") (pintype "passive"))
    )
    (net (code "46") (name "Net-(L3-PadA)") (class "Default")
      (node (ref "L3") (pin "A") (pinfunction "A_A") (pintype "passive"))
      (node (ref "R8") (pin "1") (pinfunction "1_1") (pintype "passive"))
    )
    (net (code "47") (name "Net-(ON1-PadA)") (class "Default")
      (node (ref "ON1") (pin "A") (pinfunction "A_A") (pintype "passive"))
      (node (ref "R11") (pin "1") (pinfunction "1_1") (pintype "passive"))
    )
    (net (code "48") (name "Net-(R10-Pad1)") (class "Default")
      (node (ref "R10") (pin "1") (pinfunction "1_1") (pintype "passive"))
      (node (ref "RX1") (pin "A") (pinfunction "A_A") (pintype "passive"))
    )
    (net (code "49") (name "UGND") (class "Default")
      (node (ref "C7") (pin "2") (pinfunction "2_2") (pintype "passive"))
      (node (ref "J1") (pin "P5") (pinfunction "GND_P5") (pintype "passive"))
      (node (ref "L2") (pin "1") (pinfunction "1_1") (pintype "passive"))
      (node (ref "R5") (pin "2") (pinfunction "2_2") (pintype "passive"))
      (node (ref "U1") (pin "5") (pinfunction "UGND_5") (pintype "passive"))
      (node (ref "U2") (pin "5") (pinfunction "UGND_5") (pintype "passive"))
    )
    (net (code "50") (name "VUSB") (class "Default")
      (node (ref "C10") (pin "2") (pinfunction "2_2") (pintype "passive"))
      (node (ref "C9") (pin "+") (pinfunction "+_+") (pintype "passive"))
      (node (ref "F1") (pin "1") (pinfunction "1_1") (pintype "passive"))
      (node (ref "T1") (pin "1") (pinfunction "D_1") (pintype "passive"))
      (node (ref "U1") (pin "7") (pinfunction "VBUS_7") (pintype "passive"))
      (node (ref "U2") (pin "7") (pinfunction "VBUS_7") (pintype "passive"))
    )
    (net (code "51") (name "unconnected-(ICSP1-Pad6)") (class "Default")
      (node (ref "ICSP1") (pin "6") (pinfunction "6_6") (pintype "passive+no_connect"))
    )
    (net (code "52") (name "unconnected-(J1-ID-PadP4)") (class "Default")
      (node (ref "J1") (pin "P4") (pinfunction "ID_P4") (pintype "passive+no_connect"))
    )
    (net (code "53") (name "unconnected-(J3-Pad1)") (class "Default")
      (node (ref "J3") (pin "1") (pinfunction "1_1") (pintype "passive+no_connect"))
    )
    (net (code "54") (name "unconnected-(ORIGIN1-TESTP-PadX)") (class "Default")
      (node (ref "ORIGIN1") (pin "X") (pinfunction "TESTP_X") (pintype "passive"))
    )
    (net (code "55") (name "unconnected-(R9-Pad1)") (class "Default")
      (node (ref "R9") (pin "1") (pinfunction "1_1") (pintype "passive"))
    )
    (net (code "56") (name "unconnected-(RESET1-5-GND-Pad5)") (class "Default")
      (node (ref "RESET1") (pin "5") (pinfunction "5-GND_5") (pintype "passive"))
    )
    (net (code "57") (name "unconnected-(TX1-PadA)") (class "Default")
      (node (ref "TX1") (pin "A") (pinfunction "A_A") (pintype "passive"))
    )
    (net (code "58") (name "unconnected-(TX1-PadC)") (class "Default")
      (node (ref "TX1") (pin "C") (pinfunction "C_C") (pintype "passive"))
    )
    (net (code "59") (name "unconnected-(U3-NC{slash}FB-Pad4)") (class "Default")
      (node (ref "U3") (pin "4") (pinfunction "NC/FB_4") (pintype "passive"))
    )
  )
)
